# eCog114_USB-Serial.net
KiCad netlist of a schematic drawn in EAGLE
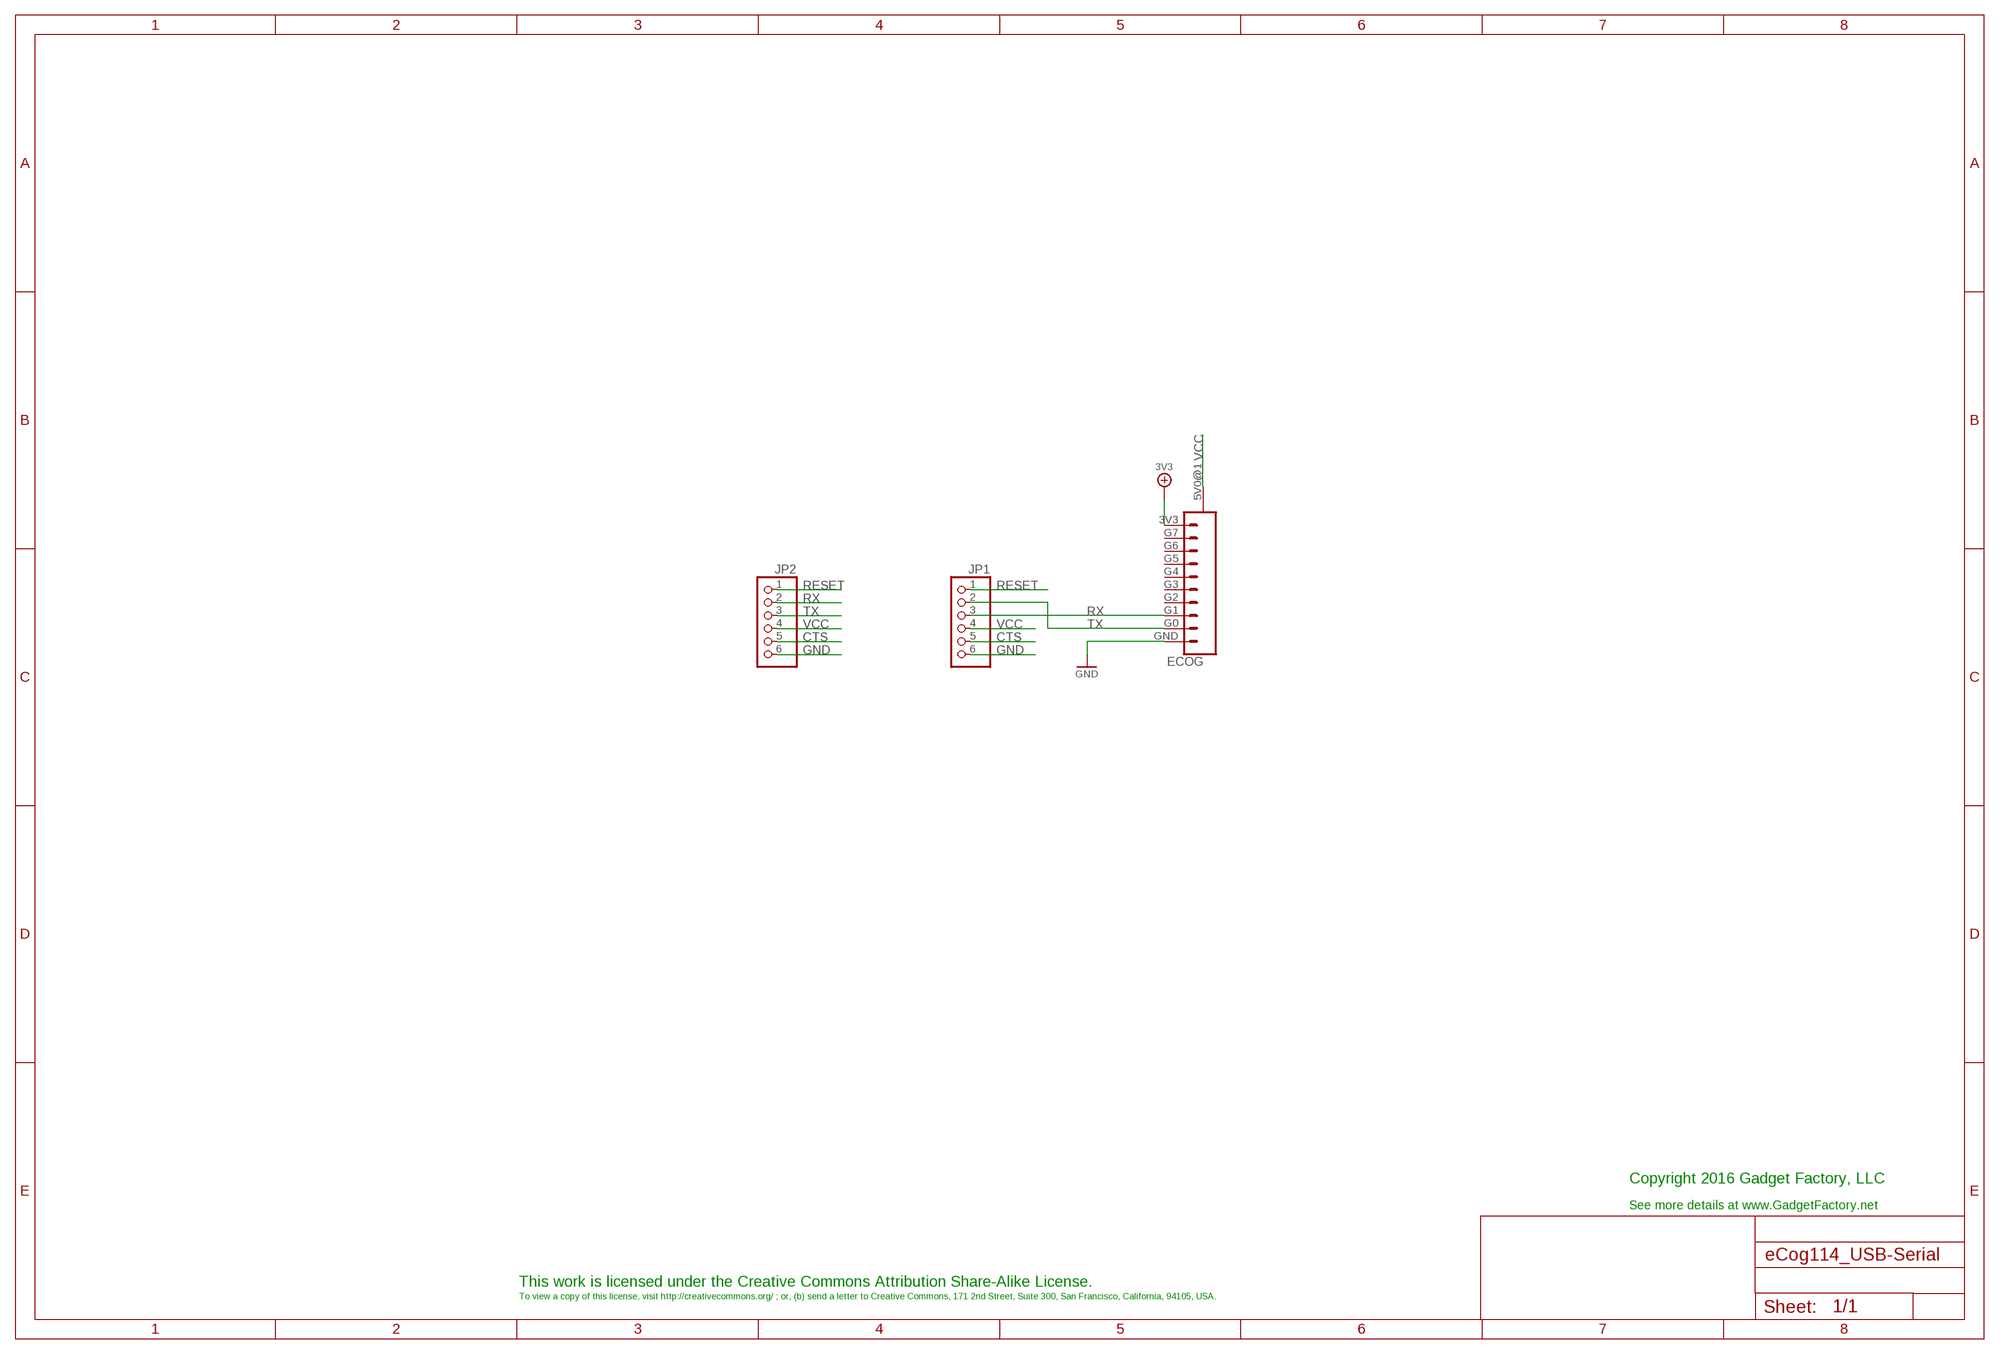
[diagram p0: schematic, sheet 1]

(export (version "E")
  (design (tool "Eeschema 10.0.6"))
  (components
    (comp (ref "ECOG")
      (value "ECOG_GENERAL_ROWECOG_GENERAL_SMD_ALT1")
      (footprint "eagle-import:ECOG_GENERAL_SMD_ALT")
      (libsource (lib "eagle-import") (part "ECOG_GENERAL_ROWECOG_GENERAL_SMD_ALT1"))
    )
    (comp (ref "JP1")
      (value "PINHD-1X6")
      (footprint "eagle-import:1X06")
      (libsource (lib "eagle-import") (part "PINHD-1X6"))
    )
    (comp (ref "JP2")
      (value "PINHD-1X6")
      (footprint "eagle-import:1X06")
      (libsource (lib "eagle-import") (part "PINHD-1X6"))
    )
  )
  (nets
    (net (code "1") (name "/CTS") (class "Default")
      (node (ref "JP1") (pin "5") (pinfunction "5_5") (pintype "passive"))
      (node (ref "JP2") (pin "5") (pinfunction "5_5") (pintype "passive"))
    )
    (net (code "2") (name "/RESET") (class "Default")
      (node (ref "JP1") (pin "1") (pinfunction "1_1") (pintype "passive"))
      (node (ref "JP2") (pin "1") (pinfunction "1_1") (pintype "passive"))
    )
    (net (code "3") (name "/RX") (class "Default")
      (node (ref "ECOG") (pin "G1") (pinfunction "G1_G1") (pintype "passive"))
      (node (ref "JP1") (pin "3") (pinfunction "3_3") (pintype "passive"))
      (node (ref "JP2") (pin "2") (pinfunction "2_2") (pintype "passive"))
    )
    (net (code "4") (name "/TX") (class "Default")
      (node (ref "ECOG") (pin "G0") (pinfunction "G0_G0") (pintype "passive"))
      (node (ref "JP1") (pin "2") (pinfunction "2_2") (pintype "passive"))
      (node (ref "JP2") (pin "3") (pinfunction "3_3") (pintype "passive"))
    )
    (net (code "5") (name "/VCC") (class "Default")
      (node (ref "ECOG") (pin "5V0@1") (pinfunction "5V0_5V0@1") (pintype "power_in"))
      (node (ref "JP1") (pin "4") (pinfunction "4_4") (pintype "passive"))
      (node (ref "JP2") (pin "4") (pinfunction "4_4") (pintype "passive"))
    )
    (net (code "6") (name "3V3") (class "Default")
      (node (ref "ECOG") (pin "3V3") (pinfunction "3V3_3V3") (pintype "power_in"))
    )
    (net (code "7") (name "GND") (class "Default")
      (node (ref "ECOG") (pin "GND") (pinfunction "GND_GND") (pintype "power_in"))
      (node (ref "JP1") (pin "6") (pinfunction "6_6") (pintype "passive"))
      (node (ref "JP2") (pin "6") (pinfunction "6_6") (pintype "passive"))
    )
    (net (code "8") (name "unconnected-(ECOG-PadG2)") (class "Default")
      (node (ref "ECOG") (pin "G2") (pinfunction "G2_G2") (pintype "passive"))
    )
    (net (code "9") (name "unconnected-(ECOG-PadG3)") (class "Default")
      (node (ref "ECOG") (pin "G3") (pinfunction "G3_G3") (pintype "passive"))
    )
    (net (code "10") (name "unconnected-(ECOG-PadG4)") (class "Default")
      (node (ref "ECOG") (pin "G4") (pinfunction "G4_G4") (pintype "passive"))
    )
    (net (code "11") (name "unconnected-(ECOG-PadG5)") (class "Default")
      (node (ref "ECOG") (pin "G5") (pinfunction "G5_G5") (pintype "passive"))
    )
    (net (code "12") (name "unconnected-(ECOG-PadG6)") (class "Default")
      (node (ref "ECOG") (pin "G6") (pinfunction "G6_G6") (pintype "passive"))
    )
    (net (code "13") (name "unconnected-(ECOG-PadG7)") (class "Default")
      (node (ref "ECOG") (pin "G7") (pinfunction "G7_G7") (pintype "passive"))
    )
  )
)
